# Sheet1.net
KiCad netlist of a schematic drawn in Altium Designer
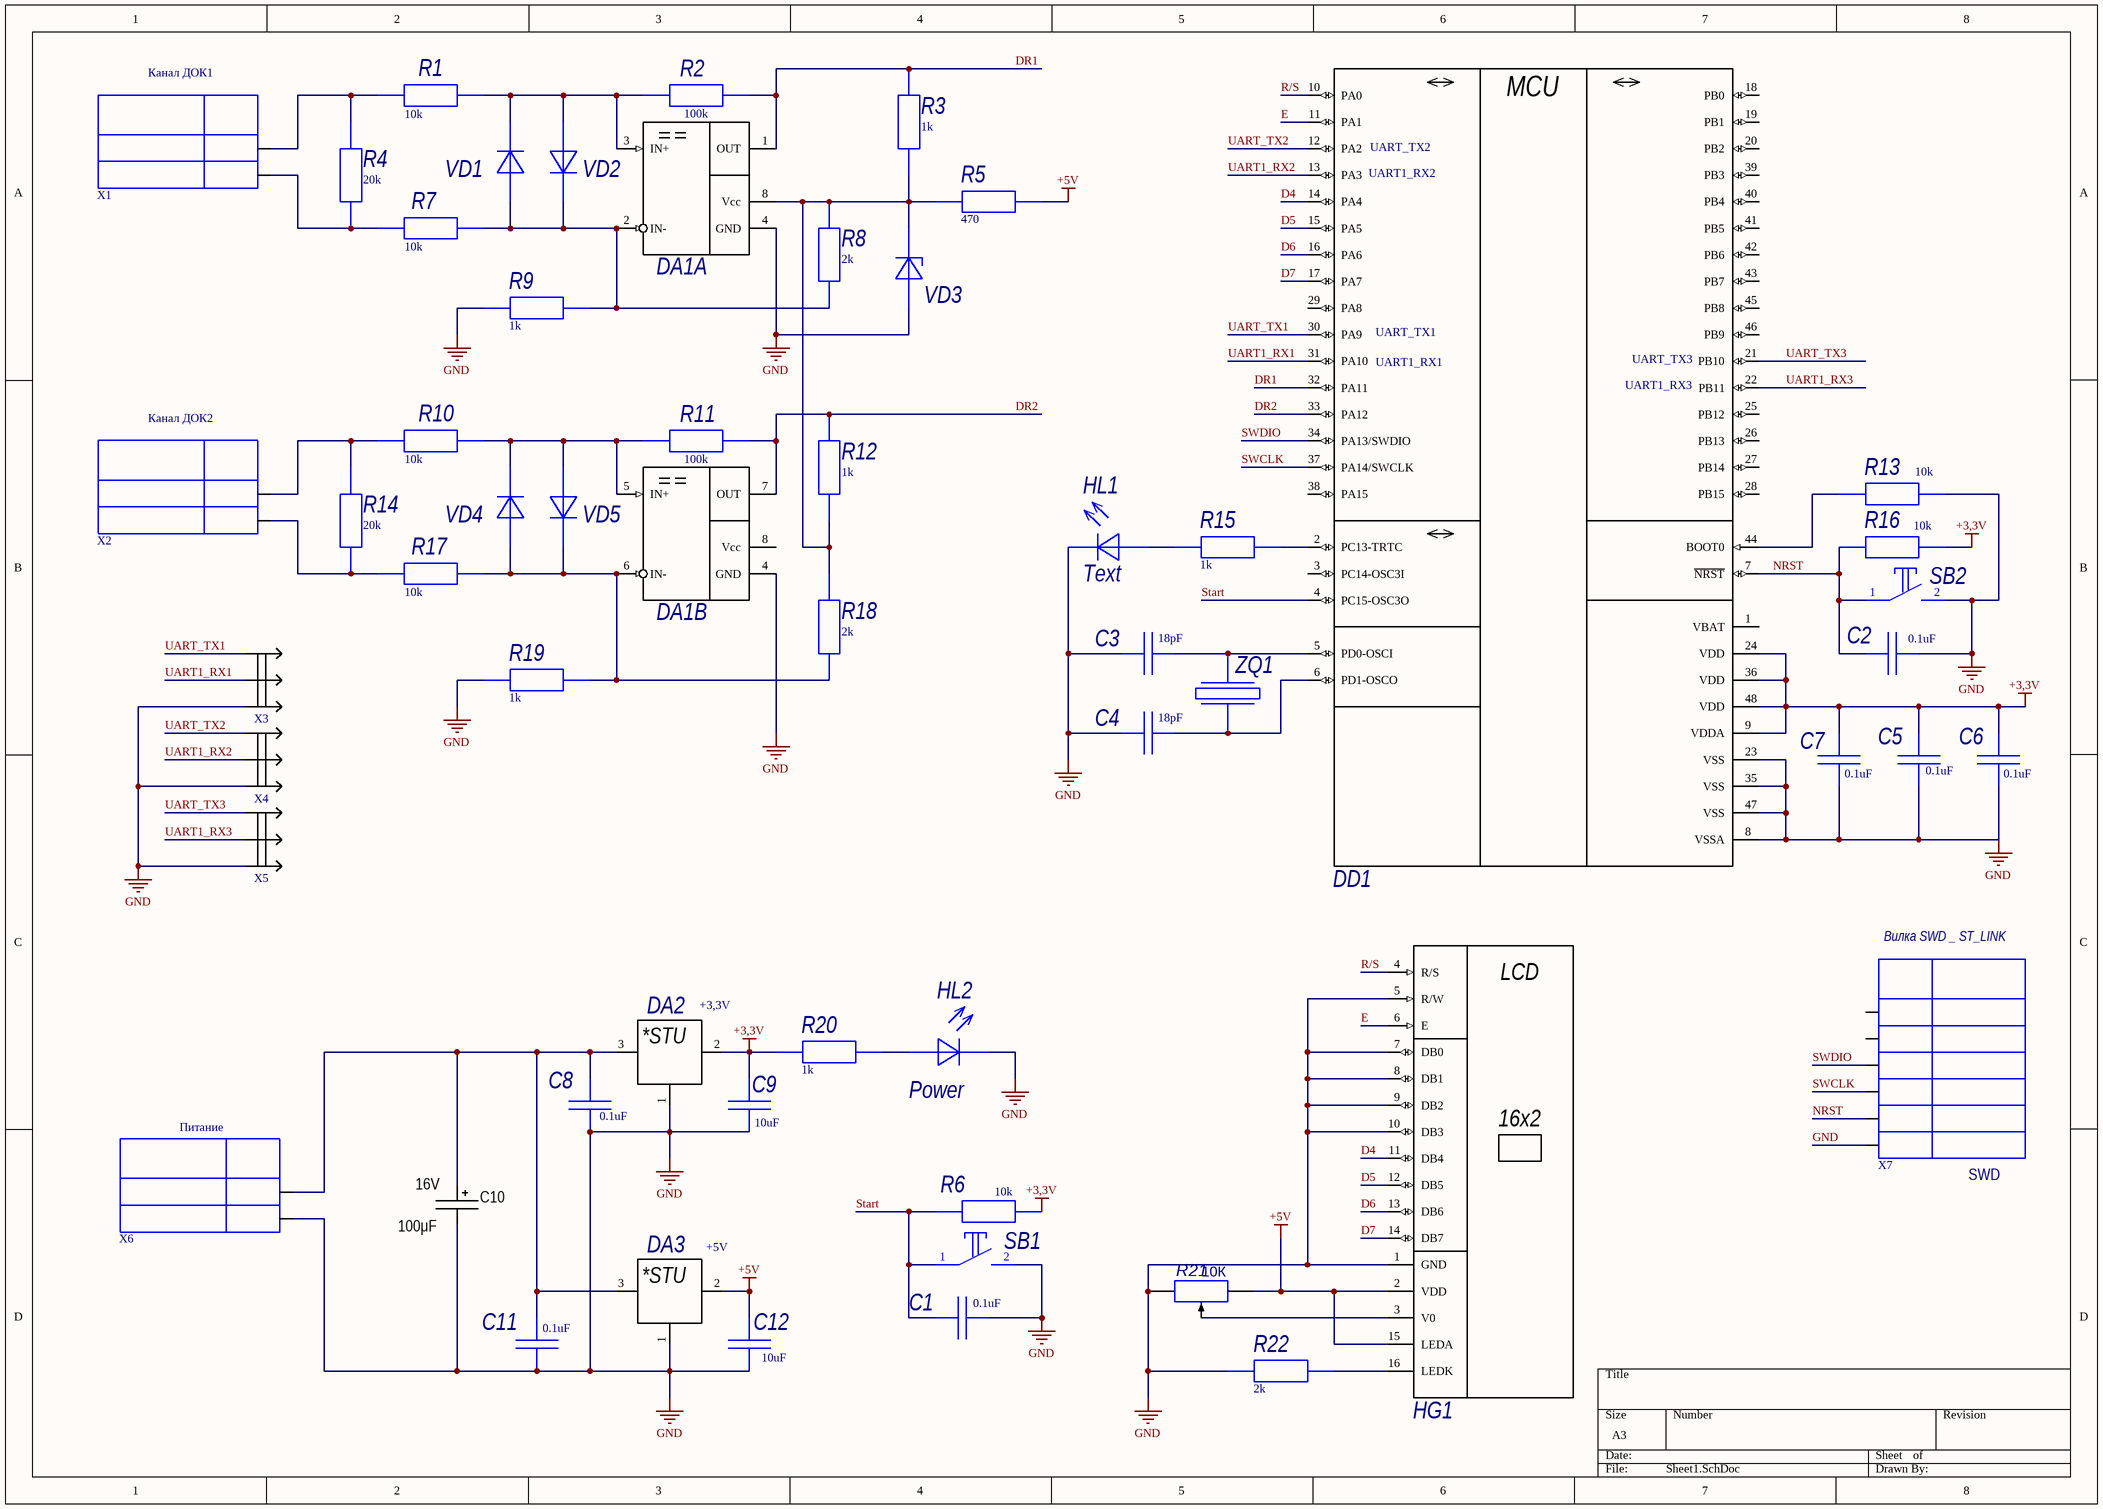
[diagram p0: Sheet1.SchDoc]

(export (version "E")
  (design (tool "Eeschema 10.0.6"))
  (components
    (comp (ref "C1")
      (value "0.1uF")
      (footprint "C0805")
      (fields
        (field (name "PART NUMBER") "GRM21BR71H104KA01L")
        (field (name "VOLTAGE") "50V")
        (field (name "TOLERANCE") "±10%")
        (field (name "PUBLISHER") "Andrew Danich")
      )
      (libsource (lib "Lib_IMP_GOST") (part "Capacitor"))
    )
    (comp (ref "C2")
      (value "0.1uF")
      (footprint "C0805")
      (fields
        (field (name "PART NUMBER") "GRM21BR71H104KA01L")
        (field (name "VOLTAGE") "50V")
        (field (name "TOLERANCE") "±10%")
        (field (name "PUBLISHER") "Andrew Danich")
      )
      (libsource (lib "Lib_IMP_GOST") (part "Capacitor"))
    )
    (comp (ref "C3")
      (value "18pF")
      (footprint "C0603")
      (fields
        (field (name "PART NUMBER") "GRM188R71E223KA01D")
        (field (name "VOLTAGE") "25V")
        (field (name "TOLERANCE") "±10%")
        (field (name "PUBLISHER") "Andrew Danich")
      )
      (libsource (lib "Lib_IMP_GOST") (part "Capacitor"))
    )
    (comp (ref "C4")
      (value "18pF")
      (footprint "C0603")
      (fields
        (field (name "PART NUMBER") "GRM188R71E223KA01D")
        (field (name "VOLTAGE") "25V")
        (field (name "TOLERANCE") "±10%")
        (field (name "PUBLISHER") "Andrew Danich")
      )
      (libsource (lib "Lib_IMP_GOST") (part "Capacitor"))
    )
    (comp (ref "C5")
      (value "0.1uF")
      (footprint "C0805")
      (fields
        (field (name "PART NUMBER") "GRM21BR71H104KA01L")
        (field (name "VOLTAGE") "50V")
        (field (name "TOLERANCE") "±10%")
        (field (name "PUBLISHER") "Andrew Danich")
      )
      (libsource (lib "Lib_IMP_GOST") (part "Capacitor"))
    )
    (comp (ref "C6")
      (value "0.1uF")
      (footprint "C0805")
      (fields
        (field (name "PART NUMBER") "GRM21BR71H104KA01L")
        (field (name "VOLTAGE") "50V")
        (field (name "TOLERANCE") "±10%")
        (field (name "PUBLISHER") "Andrew Danich")
      )
      (libsource (lib "Lib_IMP_GOST") (part "Capacitor"))
    )
    (comp (ref "C7")
      (value "0.1uF")
      (footprint "C0805")
      (fields
        (field (name "PART NUMBER") "GRM21BR71H104KA01L")
        (field (name "VOLTAGE") "50V")
        (field (name "TOLERANCE") "±10%")
        (field (name "PUBLISHER") "Andrew Danich")
      )
      (libsource (lib "Lib_IMP_GOST") (part "Capacitor"))
    )
    (comp (ref "C8")
      (value "0.1uF")
      (footprint "C0805")
      (fields
        (field (name "PART NUMBER") "GRM21BR71H104KA01L")
        (field (name "VOLTAGE") "50V")
        (field (name "TOLERANCE") "±10%")
        (field (name "PUBLISHER") "Andrew Danich")
      )
      (libsource (lib "Lib_IMP_GOST") (part "Capacitor"))
    )
    (comp (ref "C9")
      (value "10uF")
      (footprint "C0805")
      (fields
        (field (name "PART NUMBER") "GRM21BR61E106KA73L")
        (field (name "VOLTAGE") "25V")
        (field (name "TOLERANCE") "±10%")
        (field (name "PUBLISHER") "Andrew Danich")
      )
      (libsource (lib "Lib_IMP_GOST") (part "Capacitor"))
    )
    (comp (ref "C10")
      (value "100μF")
      (footprint "CAP: D5C2H11")
      (fields
        (field (name "MANUFACTURER") "Wurth")
        (field (name "PARTNUMBER") "860080475013")
        (field (name "VALUEMANUFACTURERPARTNUMBER") "Aluminium capacitor, 100μF, 16V, ±20%, 54mOhm, 14x10x5 mm, -55...+105°C")
        (field (name "VOLTAGE") "16V")
      )
      (libsource (lib "Capacitor") (part "Aluminium"))
    )
    (comp (ref "C11")
      (value "0.1uF")
      (footprint "C0805")
      (fields
        (field (name "PART NUMBER") "GRM21BR71H104KA01L")
        (field (name "VOLTAGE") "50V")
        (field (name "TOLERANCE") "±10%")
        (field (name "PUBLISHER") "Andrew Danich")
      )
      (libsource (lib "Lib_IMP_GOST") (part "Capacitor"))
    )
    (comp (ref "C12")
      (value "10uF")
      (footprint "C0805")
      (fields
        (field (name "PART NUMBER") "GRM21BR61E106KA73L")
        (field (name "VOLTAGE") "25V")
        (field (name "TOLERANCE") "±10%")
        (field (name "PUBLISHER") "Andrew Danich")
      )
      (libsource (lib "Lib_IMP_GOST") (part "Capacitor"))
    )
    (comp (ref "DA1")
      (value "COMP_2x_8p")
      (footprint "SOIC-8")
      (fields
        (field (name "PART NUMBER") "LM293AD")
        (field (name "MANUFACTURER") "Texas Instruments")
        (field (name "PUBLISHER") "Viktor Klishin")
      )
      (libsource (lib "Lib_IMP_GOST") (part "COMP_2x_8p"))
    )
    (comp (ref "DA2")
      (value "LM1117-Series")
      (footprint "SOT-223")
      (fields
        (field (name "PART NUMBER") "LM1117MPX-3.3")
        (field (name "OUTPUT VOLTAGE") "+3,3V")
        (field (name "PUBLISHER") "Andrew Danich")
      )
      (libsource (lib "Lib_IMP_GOST") (part "LM1117-Series"))
    )
    (comp (ref "DA3")
      (value "LM1117-Series")
      (footprint "SOT-223")
      (fields
        (field (name "PART NUMBER") "LM1117MPX-3.3")
        (field (name "OUTPUT VOLTAGE") "+5V")
        (field (name "PUBLISHER") "Andrew Danich")
      )
      (libsource (lib "Lib_IMP_GOST") (part "LM1117-Series"))
    )
    (comp (ref "DD1")
      (value "STM32F103Cxxx-Series")
      (footprint "LQFP-48")
      (fields
        (field (name "PART NUMBER") "STM32F103C8T6")
        (field (name "MANUFACTURER") "STMicroelectronics")
        (field (name "PUBLISHER") "Andrew Danich")
      )
      (libsource (lib "Lib_IMP_GOST") (part "STM32F103Cxxx-Series"))
    )
    (comp (ref "HG1")
      (value "QC1602AV2_0")
      (footprint "QC1602AV2_0 _PLS")
      (fields (field (name "PART NUMBER") "QC1602AV2_0 _PLS") (field (name "PUBLISHER") "Andrew Danich"))
      (libsource (lib "Library") (part "QC1602AV2_0"))
    )
    (comp (ref "HL1")
      (value "Text")
      (footprint "LD-3mm-G")
      (fields (field (name "PART NUMBER") "BL-L314UGC") (field (name "PUBLISHER") "Andrew Danich"))
      (libsource (lib "Lib_IMP_GOST") (part "Led-1"))
    )
    (comp (ref "HL2")
      (value "Power")
      (footprint "LD-3mm-R")
      (fields (field (name "PART NUMBER") "BL-L314HD") (field (name "PUBLISHER") "Andrew Danich"))
      (libsource (lib "Lib_IMP_GOST") (part "Led-1"))
    )
    (comp (ref "R1")
      (value "10k")
      (footprint "R0805")
      (fields
        (field (name "PART NUMBER") "RC0805JR-0710KL")
        (field (name "TOLERANCE") "±5%")
        (field (name "MANUFACTURER") "Yageo")
        (field (name "PUBLISHER") "Andrew Danich")
      )
      (libsource (lib "Lib_IMP_GOST") (part "Resistor"))
    )
    (comp (ref "R2")
      (value "100k")
      (footprint "R0805")
      (fields
        (field (name "PART NUMBER") "RC0805JR-0733KL")
        (field (name "TOLERANCE") "±5%")
        (field (name "MANUFACTURER") "Yageo")
        (field (name "PUBLISHER") "Andrew Danich")
      )
      (libsource (lib "Lib_IMP_GOST") (part "Resistor"))
    )
    (comp (ref "R3")
      (value "1k")
      (footprint "R0805")
      (fields
        (field (name "PART NUMBER") "RC0805JR-071KL")
        (field (name "TOLERANCE") "±5%")
        (field (name "MANUFACTURER") "Yageo")
        (field (name "PUBLISHER") "Andrew Danich")
      )
      (libsource (lib "Lib_IMP_GOST") (part "Resistor"))
    )
    (comp (ref "R4")
      (value "20k")
      (footprint "R0603")
      (fields
        (field (name "PART NUMBER") "RC0603FR-0720KL")
        (field (name "TOLERANCE") "±1%")
        (field (name "MANUFACTURER") "Yageo")
        (field (name "PUBLISHER") "Andrew Danich")
      )
      (libsource (lib "Lib_IMP_GOST") (part "Resistor"))
    )
    (comp (ref "R5")
      (value "470")
      (footprint "R0805")
      (fields
        (field (name "PART NUMBER") "RC0805JR-07470RL")
        (field (name "TOLERANCE") "±5%")
        (field (name "MANUFACTURER") "Yageo")
        (field (name "PUBLISHER") "Andrew Danich")
      )
      (libsource (lib "Lib_IMP_GOST") (part "Resistor"))
    )
    (comp (ref "R6")
      (value "10k")
      (footprint "R0805")
      (fields
        (field (name "PART NUMBER") "RC0805JR-0710KL")
        (field (name "TOLERANCE") "±5%")
        (field (name "MANUFACTURER") "Yageo")
        (field (name "PUBLISHER") "Andrew Danich")
      )
      (libsource (lib "Lib_IMP_GOST") (part "Resistor"))
    )
    (comp (ref "R7")
      (value "10k")
      (footprint "R0805")
      (fields
        (field (name "PART NUMBER") "RC0805JR-0710KL")
        (field (name "TOLERANCE") "±5%")
        (field (name "MANUFACTURER") "Yageo")
        (field (name "PUBLISHER") "Andrew Danich")
      )
      (libsource (lib "Lib_IMP_GOST") (part "Resistor"))
    )
    (comp (ref "R8")
      (value "2k")
      (footprint "R0805")
      (fields
        (field (name "PART NUMBER") "RC0805JR-072KL")
        (field (name "TOLERANCE") "±5%")
        (field (name "MANUFACTURER") "Yageo")
        (field (name "PUBLISHER") "Andrew Danich")
      )
      (libsource (lib "Lib_IMP_GOST") (part "Resistor"))
    )
    (comp (ref "R9")
      (value "1k")
      (footprint "R0805")
      (fields
        (field (name "PART NUMBER") "RC0805JR-071KL")
        (field (name "TOLERANCE") "±5%")
        (field (name "MANUFACTURER") "Yageo")
        (field (name "PUBLISHER") "Andrew Danich")
      )
      (libsource (lib "Lib_IMP_GOST") (part "Resistor"))
    )
    (comp (ref "R10")
      (value "10k")
      (footprint "R0805")
      (fields
        (field (name "PART NUMBER") "RC0805JR-0710KL")
        (field (name "TOLERANCE") "±5%")
        (field (name "MANUFACTURER") "Yageo")
        (field (name "PUBLISHER") "Andrew Danich")
      )
      (libsource (lib "Lib_IMP_GOST") (part "Resistor"))
    )
    (comp (ref "R11")
      (value "100k")
      (footprint "R0805")
      (fields
        (field (name "PART NUMBER") "RC0805JR-0733KL")
        (field (name "TOLERANCE") "±5%")
        (field (name "MANUFACTURER") "Yageo")
        (field (name "PUBLISHER") "Andrew Danich")
      )
      (libsource (lib "Lib_IMP_GOST") (part "Resistor"))
    )
    (comp (ref "R12")
      (value "1k")
      (footprint "R0805")
      (fields
        (field (name "PART NUMBER") "RC0805JR-071KL")
        (field (name "TOLERANCE") "±5%")
        (field (name "MANUFACTURER") "Yageo")
        (field (name "PUBLISHER") "Andrew Danich")
      )
      (libsource (lib "Lib_IMP_GOST") (part "Resistor"))
    )
    (comp (ref "R13")
      (value "10k")
      (footprint "R0805")
      (fields
        (field (name "PART NUMBER") "RC0805JR-0710KL")
        (field (name "TOLERANCE") "±5%")
        (field (name "MANUFACTURER") "Yageo")
        (field (name "PUBLISHER") "Andrew Danich")
      )
      (libsource (lib "Lib_IMP_GOST") (part "Resistor"))
    )
    (comp (ref "R14")
      (value "20k")
      (footprint "R0603")
      (fields
        (field (name "PART NUMBER") "RC0603FR-0720KL")
        (field (name "TOLERANCE") "±1%")
        (field (name "MANUFACTURER") "Yageo")
        (field (name "PUBLISHER") "Andrew Danich")
      )
      (libsource (lib "Lib_IMP_GOST") (part "Resistor"))
    )
    (comp (ref "R15")
      (value "1k")
      (footprint "R0805")
      (fields
        (field (name "PART NUMBER") "RC0805JR-071KL")
        (field (name "TOLERANCE") "±5%")
        (field (name "MANUFACTURER") "Yageo")
        (field (name "PUBLISHER") "Andrew Danich")
      )
      (libsource (lib "Lib_IMP_GOST") (part "Resistor"))
    )
    (comp (ref "R16")
      (value "10k")
      (footprint "R0805")
      (fields
        (field (name "PART NUMBER") "RC0805JR-0710KL")
        (field (name "TOLERANCE") "±5%")
        (field (name "MANUFACTURER") "Yageo")
        (field (name "PUBLISHER") "Andrew Danich")
      )
      (libsource (lib "Lib_IMP_GOST") (part "Resistor"))
    )
    (comp (ref "R17")
      (value "10k")
      (footprint "R0805")
      (fields
        (field (name "PART NUMBER") "RC0805JR-0710KL")
        (field (name "TOLERANCE") "±5%")
        (field (name "MANUFACTURER") "Yageo")
        (field (name "PUBLISHER") "Andrew Danich")
      )
      (libsource (lib "Lib_IMP_GOST") (part "Resistor"))
    )
    (comp (ref "R18")
      (value "2k")
      (footprint "R0805")
      (fields
        (field (name "PART NUMBER") "RC0805JR-072KL")
        (field (name "TOLERANCE") "±5%")
        (field (name "MANUFACTURER") "Yageo")
        (field (name "PUBLISHER") "Andrew Danich")
      )
      (libsource (lib "Lib_IMP_GOST") (part "Resistor"))
    )
    (comp (ref "R19")
      (value "1k")
      (footprint "R0805")
      (fields
        (field (name "PART NUMBER") "RC0805JR-071KL")
        (field (name "TOLERANCE") "±5%")
        (field (name "MANUFACTURER") "Yageo")
        (field (name "PUBLISHER") "Andrew Danich")
      )
      (libsource (lib "Lib_IMP_GOST") (part "Resistor"))
    )
    (comp (ref "R20")
      (value "1k")
      (footprint "R0805")
      (fields
        (field (name "PART NUMBER") "RC0805JR-071KL")
        (field (name "TOLERANCE") "±5%")
        (field (name "MANUFACTURER") "Yageo")
        (field (name "PUBLISHER") "Andrew Danich")
      )
      (libsource (lib "Lib_IMP_GOST") (part "Resistor"))
    )
    (comp (ref "R21")
      (value "10К")
      (footprint "CA9V")
      (fields (field (name "PART NUMBER") "CA9PV10-10KA2020") (field (name "Comment") "Potentiometer"))
      (libsource (lib "Library") (part "Potentiometer"))
    )
    (comp (ref "R22")
      (value "2k")
      (footprint "R0805")
      (fields
        (field (name "PART NUMBER") "RC0805JR-072KL")
        (field (name "TOLERANCE") "±5%")
        (field (name "MANUFACTURER") "Yageo")
        (field (name "PUBLISHER") "Andrew Danich")
      )
      (libsource (lib "Lib_IMP_GOST") (part "Resistor"))
    )
    (comp (ref "SB1")
      (value "Text")
      (footprint "TS-A3PS")
      (fields (field (name "PART NUMBER") "TS-A3PS-130") (field (name "PUBLISHER") "Andrew Danich"))
      (libsource (lib "Lib_IMP_GOST") (part "BT-01x-01p"))
    )
    (comp (ref "SB2")
      (value "Text")
      (footprint "TS-A3PS")
      (fields (field (name "PART NUMBER") "TS-A3PS-130") (field (name "PUBLISHER") "Andrew Danich"))
      (libsource (lib "Lib_IMP_GOST") (part "BT-01x-01p"))
    )
    (comp (ref "VD1")
      (value "Diode")
      (footprint "DO-214AC")
      (fields (field (name "PART NUMBER") "ES1G") (field (name "PUBLISHER") "Andrew Danich"))
      (libsource (lib "Lib_IMP_GOST") (part "Diode"))
    )
    (comp (ref "VD2")
      (value "Diode")
      (footprint "DO-214AC")
      (fields (field (name "PART NUMBER") "ES1G") (field (name "PUBLISHER") "Andrew Danich"))
      (libsource (lib "Lib_IMP_GOST") (part "Diode"))
    )
    (comp (ref "VD3")
      (value "Zener")
      (footprint "SOD-80")
      (fields (field (name "PART NUMBER") "BZV55-C5V1") (field (name "PUBLISHER") "Andrew Danich"))
      (libsource (lib "Lib_IMP_GOST") (part "Zener"))
    )
    (comp (ref "VD4")
      (value "Diode")
      (footprint "DO-214AC")
      (fields (field (name "PART NUMBER") "ES1G") (field (name "PUBLISHER") "Andrew Danich"))
      (libsource (lib "Lib_IMP_GOST") (part "Diode"))
    )
    (comp (ref "VD5")
      (value "Diode")
      (footprint "DO-214AC")
      (fields (field (name "PART NUMBER") "ES1G") (field (name "PUBLISHER") "Andrew Danich"))
      (libsource (lib "Lib_IMP_GOST") (part "Diode"))
    )
    (comp (ref "X1")
      (value "Канал ДОК1")
      (footprint "2EDGV-5.0-02P-14")
      (libsource (lib "Connector PCB") (part "Вилка 2EDGV-5.08-02P"))
    )
    (comp (ref "X2")
      (value "Канал ДОК2")
      (footprint "2EDGV-5.0-02P-14")
      (libsource (lib "Connector PCB") (part "Вилка 2EDGV-5.08-02P"))
    )
    (comp (ref "X3")
      (value "Разъем PLS-3")
      (footprint "HDR1X3")
      (description "Вилка штыревая 2.54мм 1x3 прямая в отверстия")
      (libsource (lib "Connector PCB") (part "Вилка 3pin"))
    )
    (comp (ref "X4")
      (value "Разъем PLS-3")
      (footprint "HDR1X3")
      (description "Вилка штыревая 2.54мм 1x3 прямая в отверстия")
      (libsource (lib "Connector PCB") (part "Вилка 3pin"))
    )
    (comp (ref "X5")
      (value "Разъем PLS-3")
      (footprint "HDR1X3")
      (description "Вилка штыревая 2.54мм 1x3 прямая в отверстия")
      (libsource (lib "Connector PCB") (part "Вилка 3pin"))
    )
    (comp (ref "X6")
      (value "Питание")
      (footprint "2EDGV-5.0-02P-14")
      (libsource (lib "Connector PCB") (part "Вилка 2EDGV-5.08-02P"))
    )
    (comp (ref "X7")
      (value "Вилка SWD _ ST_LINK")
      (footprint "PLD6")
      (description "Вилка 2x3 pin 2.54 mm в отверстия")
      (fields (field (name "ALTIUM_VALUE") "SWD"))
      (libsource (lib "Connector PCB") (part "Вилка SWD _ ST_LINK"))
    )
    (comp (ref "ZQ1")
      (value "Crystal")
      (footprint "HC-49SM")
      (fields (field (name "PART NUMBER") "HC49SM-8.000MHz-20pF") (field (name "PUBLISHER") "Andrew Danich"))
      (libsource (lib "Lib_IMP_GOST") (part "Crystal"))
    )
  )
  (nets
    (net (code "1") (name "+3,3V") (class "Default")
      (node (ref "C5") (pin "2") (pinfunction "2_2") (pintype "passive"))
      (node (ref "C6") (pin "2") (pinfunction "2_2") (pintype "passive"))
      (node (ref "C7") (pin "2") (pinfunction "2_2") (pintype "passive"))
      (node (ref "C9") (pin "2") (pinfunction "2_2") (pintype "passive"))
      (node (ref "DA2") (pin "2") (pinfunction "Out_2") (pintype "passive"))
      (node (ref "DD1") (pin "24") (pinfunction "VDD_24") (pintype "power_in"))
      (node (ref "DD1") (pin "36") (pinfunction "VDD_36") (pintype "power_in"))
      (node (ref "DD1") (pin "48") (pinfunction "VDD_48") (pintype "power_in"))
      (node (ref "DD1") (pin "9") (pinfunction "VDDA_9") (pintype "power_in"))
      (node (ref "R16") (pin "1") (pinfunction "1_1") (pintype "passive"))
      (node (ref "R20") (pin "1") (pinfunction "1_1") (pintype "passive"))
      (node (ref "R6") (pin "1") (pinfunction "1_1") (pintype "passive"))
    )
    (net (code "2") (name "+5V") (class "Default")
      (node (ref "C12") (pin "2") (pinfunction "2_2") (pintype "passive"))
      (node (ref "DA3") (pin "2") (pinfunction "Out_2") (pintype "passive"))
      (node (ref "HG1") (pin "15") (pinfunction "LEDA_15") (pintype "power_in"))
      (node (ref "HG1") (pin "2") (pinfunction "VDD_2") (pintype "power_in"))
      (node (ref "R21") (pin "1") (pinfunction "1_1") (pintype "passive"))
      (node (ref "R5") (pin "2") (pinfunction "2_2") (pintype "passive"))
    )
    (net (code "3") (name "/D4") (class "Default")
      (node (ref "DD1") (pin "14") (pinfunction "PA4_14") (pintype "bidirectional"))
      (node (ref "HG1") (pin "11") (pinfunction "DB4_11") (pintype "bidirectional"))
    )
    (net (code "4") (name "/D5") (class "Default")
      (node (ref "DD1") (pin "15") (pinfunction "PA5_15") (pintype "bidirectional"))
      (node (ref "HG1") (pin "12") (pinfunction "DB5_12") (pintype "bidirectional"))
    )
    (net (code "5") (name "/D6") (class "Default")
      (node (ref "DD1") (pin "16") (pinfunction "PA6_16") (pintype "bidirectional"))
      (node (ref "HG1") (pin "13") (pinfunction "DB6_13") (pintype "bidirectional"))
    )
    (net (code "6") (name "/D7") (class "Default")
      (node (ref "DD1") (pin "17") (pinfunction "PA7_17") (pintype "bidirectional"))
      (node (ref "HG1") (pin "14") (pinfunction "DB7_14") (pintype "bidirectional"))
    )
    (net (code "7") (name "/DR1") (class "Default")
      (node (ref "DA1") (pin "1") (pinfunction "OUT_1") (pintype "open_collector"))
      (node (ref "DD1") (pin "32") (pinfunction "PA11_32") (pintype "bidirectional"))
      (node (ref "R2") (pin "2") (pinfunction "2_2") (pintype "passive"))
      (node (ref "R3") (pin "2") (pinfunction "2_2") (pintype "passive"))
    )
    (net (code "8") (name "/DR2") (class "Default")
      (node (ref "DA1") (pin "7") (pinfunction "OUT_7") (pintype "open_collector"))
      (node (ref "DD1") (pin "33") (pinfunction "PA12_33") (pintype "bidirectional"))
      (node (ref "R11") (pin "2") (pinfunction "2_2") (pintype "passive"))
      (node (ref "R12") (pin "2") (pinfunction "2_2") (pintype "passive"))
    )
    (net (code "9") (name "/E") (class "Default")
      (node (ref "DD1") (pin "11") (pinfunction "PA1_11") (pintype "bidirectional"))
      (node (ref "HG1") (pin "6") (pinfunction "E_6") (pintype "input"))
    )
    (net (code "10") (name "/NRST") (class "Default")
      (node (ref "C2") (pin "2") (pinfunction "2_2") (pintype "passive"))
      (node (ref "DD1") (pin "7") (pinfunction "~{NRST}_7") (pintype "bidirectional"))
      (node (ref "R16") (pin "2") (pinfunction "2_2") (pintype "passive"))
      (node (ref "SB2") (pin "1") (pintype "passive"))
      (node (ref "X7") (pin "5") (pintype "passive"))
    )
    (net (code "11") (name "/R{slash}S") (class "Default")
      (node (ref "DD1") (pin "10") (pinfunction "PA0_10") (pintype "bidirectional"))
      (node (ref "HG1") (pin "4") (pinfunction "R/S_4") (pintype "input"))
    )
    (net (code "12") (name "/SWCLK") (class "Default")
      (node (ref "DD1") (pin "37") (pinfunction "PA14/SWCLK_37") (pintype "bidirectional"))
      (node (ref "X7") (pin "4") (pintype "passive"))
    )
    (net (code "13") (name "/SWDIO") (class "Default")
      (node (ref "DD1") (pin "34") (pinfunction "PA13/SWDIO_34") (pintype "bidirectional"))
      (node (ref "X7") (pin "3") (pinfunction "GND_3") (pintype "passive"))
    )
    (net (code "14") (name "/Start") (class "Default")
      (node (ref "C1") (pin "2") (pinfunction "2_2") (pintype "passive"))
      (node (ref "DD1") (pin "4") (pinfunction "PC15-OSC3O_4") (pintype "bidirectional"))
      (node (ref "R6") (pin "2") (pinfunction "2_2") (pintype "passive"))
      (node (ref "SB1") (pin "1") (pintype "passive"))
    )
    (net (code "15") (name "/UART1_RX1") (class "Default")
      (node (ref "DD1") (pin "31") (pinfunction "PA10_31") (pintype "bidirectional"))
      (node (ref "X3") (pin "2") (pintype "passive"))
    )
    (net (code "16") (name "/UART1_RX2") (class "Default")
      (node (ref "DD1") (pin "13") (pinfunction "PA3_13") (pintype "bidirectional"))
      (node (ref "X4") (pin "2") (pintype "passive"))
    )
    (net (code "17") (name "/UART1_RX3") (class "Default")
      (node (ref "DD1") (pin "22") (pinfunction "PB11_22") (pintype "bidirectional"))
      (node (ref "X5") (pin "2") (pintype "passive"))
    )
    (net (code "18") (name "/UART_TX1") (class "Default")
      (node (ref "DD1") (pin "30") (pinfunction "PA9_30") (pintype "bidirectional"))
      (node (ref "X3") (pin "3") (pintype "passive"))
    )
    (net (code "19") (name "/UART_TX2") (class "Default")
      (node (ref "DD1") (pin "12") (pinfunction "PA2_12") (pintype "bidirectional"))
      (node (ref "X4") (pin "3") (pintype "passive"))
    )
    (net (code "20") (name "/UART_TX3") (class "Default")
      (node (ref "DD1") (pin "21") (pinfunction "PB10_21") (pintype "bidirectional"))
      (node (ref "X5") (pin "3") (pintype "passive"))
    )
    (net (code "21") (name "GND") (class "Default")
      (node (ref "C1") (pin "1") (pinfunction "1_1") (pintype "passive"))
      (node (ref "C10") (pin "2") (pinfunction "2_2") (pintype "power_in"))
      (node (ref "C11") (pin "1") (pinfunction "1_1") (pintype "passive"))
      (node (ref "C12") (pin "1") (pinfunction "1_1") (pintype "passive"))
      (node (ref "C2") (pin "1") (pinfunction "1_1") (pintype "passive"))
      (node (ref "C3") (pin "1") (pinfunction "1_1") (pintype "passive"))
      (node (ref "C4") (pin "1") (pinfunction "1_1") (pintype "passive"))
      (node (ref "C5") (pin "1") (pinfunction "1_1") (pintype "passive"))
      (node (ref "C6") (pin "1") (pinfunction "1_1") (pintype "passive"))
      (node (ref "C7") (pin "1") (pinfunction "1_1") (pintype "passive"))
      (node (ref "C8") (pin "1") (pinfunction "1_1") (pintype "passive"))
      (node (ref "C9") (pin "1") (pinfunction "1_1") (pintype "passive"))
      (node (ref "DA1") (pin "4") (pinfunction "GND_4") (pintype "power_in"))
      (node (ref "DA2") (pin "1") (pinfunction "Adj/GND_1") (pintype "passive"))
      (node (ref "DA3") (pin "1") (pinfunction "Adj/GND_1") (pintype "passive"))
      (node (ref "DD1") (pin "23") (pinfunction "VSS_23") (pintype "power_in"))
      (node (ref "DD1") (pin "35") (pinfunction "VSS_35") (pintype "power_in"))
      (node (ref "DD1") (pin "47") (pinfunction "VSS_47") (pintype "power_in"))
      (node (ref "DD1") (pin "8") (pinfunction "VSSA_8") (pintype "power_in"))
      (node (ref "HG1") (pin "1") (pinfunction "GND_1") (pintype "power_in"))
      (node (ref "HG1") (pin "10") (pinfunction "DB3_10") (pintype "bidirectional"))
      (node (ref "HG1") (pin "5") (pinfunction "R/W_5") (pintype "input"))
      (node (ref "HG1") (pin "7") (pinfunction "DB0_7") (pintype "bidirectional"))
      (node (ref "HG1") (pin "8") (pinfunction "DB1_8") (pintype "bidirectional"))
      (node (ref "HG1") (pin "9") (pinfunction "DB2_9") (pintype "bidirectional"))
      (node (ref "HL1") (pin "2") (pinfunction "К_2") (pintype "passive"))
      (node (ref "HL2") (pin "2") (pinfunction "К_2") (pintype "passive"))
      (node (ref "R13") (pin "1") (pinfunction "1_1") (pintype "passive"))
      (node (ref "R19") (pin "1") (pinfunction "1_1") (pintype "passive"))
      (node (ref "R21") (pin "2") (pinfunction "2_2") (pintype "passive"))
      (node (ref "R22") (pin "2") (pinfunction "2_2") (pintype "passive"))
      (node (ref "R9") (pin "1") (pinfunction "1_1") (pintype "passive"))
      (node (ref "SB1") (pin "2") (pintype "passive"))
      (node (ref "SB2") (pin "2") (pintype "passive"))
      (node (ref "VD3") (pin "1") (pinfunction "А_1") (pintype "passive"))
      (node (ref "X3") (pin "1") (pintype "passive"))
      (node (ref "X4") (pin "1") (pintype "passive"))
      (node (ref "X5") (pin "1") (pintype "passive"))
      (node (ref "X6") (pin "2") (pinfunction "PIN1_2") (pintype "passive"))
      (node (ref "X7") (pin "6") (pintype "passive"))
    )
    (net (code "22") (name "Net-(DA1A-IN+)") (class "Default")
      (node (ref "DA1") (pin "3") (pinfunction "IN+_3") (pintype "input"))
      (node (ref "R1") (pin "2") (pinfunction "2_2") (pintype "passive"))
      (node (ref "R2") (pin "1") (pinfunction "1_1") (pintype "passive"))
      (node (ref "VD1") (pin "2") (pinfunction "К_2") (pintype "passive"))
      (node (ref "VD2") (pin "1") (pinfunction "А_1") (pintype "passive"))
    )
    (net (code "23") (name "Net-(DA1A-IN-)") (class "Default")
      (node (ref "DA1") (pin "2") (pinfunction "IN-_2") (pintype "input"))
      (node (ref "R7") (pin "2") (pinfunction "2_2") (pintype "passive"))
      (node (ref "R8") (pin "1") (pinfunction "1_1") (pintype "passive"))
      (node (ref "R9") (pin "2") (pinfunction "2_2") (pintype "passive"))
      (node (ref "VD1") (pin "1") (pinfunction "А_1") (pintype "passive"))
      (node (ref "VD2") (pin "2") (pinfunction "К_2") (pintype "passive"))
    )
    (net (code "24") (name "Net-(DA1A-Vcc)") (class "Default")
      (node (ref "DA1") (pin "8") (pinfunction "Vcc_8") (pintype "power_in"))
      (node (ref "R12") (pin "1") (pinfunction "1_1") (pintype "passive"))
      (node (ref "R18") (pin "2") (pinfunction "2_2") (pintype "passive"))
      (node (ref "R3") (pin "1") (pinfunction "1_1") (pintype "passive"))
      (node (ref "R5") (pin "1") (pinfunction "1_1") (pintype "passive"))
      (node (ref "R8") (pin "2") (pinfunction "2_2") (pintype "passive"))
      (node (ref "VD3") (pin "2") (pinfunction "К_2") (pintype "passive"))
    )
    (net (code "25") (name "Net-(DA1B-IN+)") (class "Default")
      (node (ref "DA1") (pin "5") (pinfunction "IN+_5") (pintype "input"))
      (node (ref "R10") (pin "2") (pinfunction "2_2") (pintype "passive"))
      (node (ref "R11") (pin "1") (pinfunction "1_1") (pintype "passive"))
      (node (ref "VD4") (pin "2") (pinfunction "К_2") (pintype "passive"))
      (node (ref "VD5") (pin "1") (pinfunction "А_1") (pintype "passive"))
    )
    (net (code "26") (name "Net-(DA1B-IN-)") (class "Default")
      (node (ref "DA1") (pin "6") (pinfunction "IN-_6") (pintype "input"))
      (node (ref "R17") (pin "2") (pinfunction "2_2") (pintype "passive"))
      (node (ref "R18") (pin "1") (pinfunction "1_1") (pintype "passive"))
      (node (ref "R19") (pin "2") (pinfunction "2_2") (pintype "passive"))
      (node (ref "VD4") (pin "1") (pinfunction "А_1") (pintype "passive"))
      (node (ref "VD5") (pin "2") (pinfunction "К_2") (pintype "passive"))
    )
    (net (code "27") (name "Net-(DA2-In)") (class "Default")
      (node (ref "C10") (pin "1") (pinfunction "1_1") (pintype "power_in"))
      (node (ref "C11") (pin "2") (pinfunction "2_2") (pintype "passive"))
      (node (ref "C8") (pin "2") (pinfunction "2_2") (pintype "passive"))
      (node (ref "DA2") (pin "3") (pinfunction "In_3") (pintype "passive"))
      (node (ref "DA3") (pin "3") (pinfunction "In_3") (pintype "passive"))
      (node (ref "X6") (pin "1") (pinfunction "PIN2_1") (pintype "passive"))
    )
    (net (code "28") (name "Net-(DD1-BOOT0)") (class "Default")
      (node (ref "DD1") (pin "44") (pinfunction "BOOT0_44") (pintype "input"))
      (node (ref "R13") (pin "2") (pinfunction "2_2") (pintype "passive"))
    )
    (net (code "29") (name "Net-(DD1-PC13-TRTC)") (class "Default")
      (node (ref "DD1") (pin "2") (pinfunction "PC13-TRTC_2") (pintype "bidirectional"))
      (node (ref "R15") (pin "1") (pinfunction "1_1") (pintype "passive"))
    )
    (net (code "30") (name "Net-(DD1-PD0-OSCI)") (class "Default")
      (node (ref "C3") (pin "2") (pinfunction "2_2") (pintype "passive"))
      (node (ref "DD1") (pin "5") (pinfunction "PD0-OSCI_5") (pintype "bidirectional"))
      (node (ref "ZQ1") (pin "3") (pinfunction "3_3") (pintype "passive"))
    )
    (net (code "31") (name "Net-(DD1-PD1-OSCO)") (class "Default")
      (node (ref "C4") (pin "2") (pinfunction "2_2") (pintype "passive"))
      (node (ref "DD1") (pin "6") (pinfunction "PD1-OSCO_6") (pintype "bidirectional"))
      (node (ref "ZQ1") (pin "1") (pinfunction "1_1") (pintype "passive"))
    )
    (net (code "32") (name "Net-(HG1-LEDK)") (class "Default")
      (node (ref "HG1") (pin "16") (pinfunction "LEDK_16") (pintype "power_in"))
      (node (ref "R22") (pin "1") (pinfunction "1_1") (pintype "passive"))
    )
    (net (code "33") (name "Net-(HG1-V0)") (class "Default")
      (node (ref "HG1") (pin "3") (pinfunction "V0_3") (pintype "power_in"))
      (node (ref "R21") (pin "3") (pinfunction "3_3") (pintype "passive"))
    )
    (net (code "34") (name "Net-(HL1-А)") (class "Default")
      (node (ref "HL1") (pin "1") (pinfunction "А_1") (pintype "passive"))
      (node (ref "R15") (pin "2") (pinfunction "2_2") (pintype "passive"))
    )
    (net (code "35") (name "Net-(HL2-А)") (class "Default")
      (node (ref "HL2") (pin "1") (pinfunction "А_1") (pintype "passive"))
      (node (ref "R20") (pin "2") (pinfunction "2_2") (pintype "passive"))
    )
    (net (code "36") (name "Net-(X1-PIN1)") (class "Default")
      (node (ref "R4") (pin "1") (pinfunction "1_1") (pintype "passive"))
      (node (ref "R7") (pin "1") (pinfunction "1_1") (pintype "passive"))
      (node (ref "X1") (pin "2") (pinfunction "PIN1_2") (pintype "passive"))
    )
    (net (code "37") (name "Net-(X1-PIN2)") (class "Default")
      (node (ref "R1") (pin "1") (pinfunction "1_1") (pintype "passive"))
      (node (ref "R4") (pin "2") (pinfunction "2_2") (pintype "passive"))
      (node (ref "X1") (pin "1") (pinfunction "PIN2_1") (pintype "passive"))
    )
    (net (code "38") (name "Net-(X2-PIN1)") (class "Default")
      (node (ref "R14") (pin "1") (pinfunction "1_1") (pintype "passive"))
      (node (ref "R17") (pin "1") (pinfunction "1_1") (pintype "passive"))
      (node (ref "X2") (pin "2") (pinfunction "PIN1_2") (pintype "passive"))
    )
    (net (code "39") (name "Net-(X2-PIN2)") (class "Default")
      (node (ref "R10") (pin "1") (pinfunction "1_1") (pintype "passive"))
      (node (ref "R14") (pin "2") (pinfunction "2_2") (pintype "passive"))
      (node (ref "X2") (pin "1") (pinfunction "PIN2_1") (pintype "passive"))
    )
    (net (code "40") (name "unconnected-(DA1B-Vcc-Pad8)") (class "Default")
      (node (ref "DA1") (pin "8") (pinfunction "Vcc_8") (pintype "power_in"))
    )
    (net (code "41") (name "unconnected-(DD1-PA8-Pad29)") (class "Default")
      (node (ref "DD1") (pin "29") (pinfunction "PA8_29") (pintype "bidirectional"))
    )
    (net (code "42") (name "unconnected-(DD1-PA15-Pad38)") (class "Default")
      (node (ref "DD1") (pin "38") (pinfunction "PA15_38") (pintype "bidirectional"))
    )
    (net (code "43") (name "unconnected-(DD1-PB0-Pad18)") (class "Default")
      (node (ref "DD1") (pin "18") (pinfunction "PB0_18") (pintype "bidirectional"))
    )
    (net (code "44") (name "unconnected-(DD1-PB1-Pad19)") (class "Default")
      (node (ref "DD1") (pin "19") (pinfunction "PB1_19") (pintype "bidirectional"))
    )
    (net (code "45") (name "unconnected-(DD1-PB2-Pad20)") (class "Default")
      (node (ref "DD1") (pin "20") (pinfunction "PB2_20") (pintype "bidirectional"))
    )
    (net (code "46") (name "unconnected-(DD1-PB3-Pad39)") (class "Default")
      (node (ref "DD1") (pin "39") (pinfunction "PB3_39") (pintype "bidirectional"))
    )
    (net (code "47") (name "unconnected-(DD1-PB4-Pad40)") (class "Default")
      (node (ref "DD1") (pin "40") (pinfunction "PB4_40") (pintype "bidirectional"))
    )
    (net (code "48") (name "unconnected-(DD1-PB5-Pad41)") (class "Default")
      (node (ref "DD1") (pin "41") (pinfunction "PB5_41") (pintype "bidirectional"))
    )
    (net (code "49") (name "unconnected-(DD1-PB6-Pad42)") (class "Default")
      (node (ref "DD1") (pin "42") (pinfunction "PB6_42") (pintype "bidirectional"))
    )
    (net (code "50") (name "unconnected-(DD1-PB7-Pad43)") (class "Default")
      (node (ref "DD1") (pin "43") (pinfunction "PB7_43") (pintype "bidirectional"))
    )
    (net (code "51") (name "unconnected-(DD1-PB8-Pad45)") (class "Default")
      (node (ref "DD1") (pin "45") (pinfunction "PB8_45") (pintype "bidirectional"))
    )
    (net (code "52") (name "unconnected-(DD1-PB9-Pad46)") (class "Default")
      (node (ref "DD1") (pin "46") (pinfunction "PB9_46") (pintype "bidirectional"))
    )
    (net (code "53") (name "unconnected-(DD1-PB12-Pad25)") (class "Default")
      (node (ref "DD1") (pin "25") (pinfunction "PB12_25") (pintype "bidirectional"))
    )
    (net (code "54") (name "unconnected-(DD1-PB13-Pad26)") (class "Default")
      (node (ref "DD1") (pin "26") (pinfunction "PB13_26") (pintype "bidirectional"))
    )
    (net (code "55") (name "unconnected-(DD1-PB14-Pad27)") (class "Default")
      (node (ref "DD1") (pin "27") (pinfunction "PB14_27") (pintype "bidirectional"))
    )
    (net (code "56") (name "unconnected-(DD1-PB15-Pad28)") (class "Default")
      (node (ref "DD1") (pin "28") (pinfunction "PB15_28") (pintype "bidirectional"))
    )
    (net (code "57") (name "unconnected-(DD1-PC14-OSC3I-Pad3)") (class "Default")
      (node (ref "DD1") (pin "3") (pinfunction "PC14-OSC3I_3") (pintype "bidirectional"))
    )
    (net (code "58") (name "unconnected-(DD1-VBAT-Pad1)") (class "Default")
      (node (ref "DD1") (pin "1") (pinfunction "VBAT_1") (pintype "power_in"))
    )
    (net (code "59") (name "unconnected-(X7-TDO-Pad2)") (class "Default")
      (node (ref "X7") (pin "2") (pinfunction "TDO_2") (pintype "passive"))
    )
    (net (code "60") (name "unconnected-(X7-VCC-Pad1)") (class "Default")
      (node (ref "X7") (pin "1") (pinfunction "VCC_1") (pintype "passive"))
    )
  )
)
